# rom.net
KiCad netlist of a schematic drawn in EAGLE
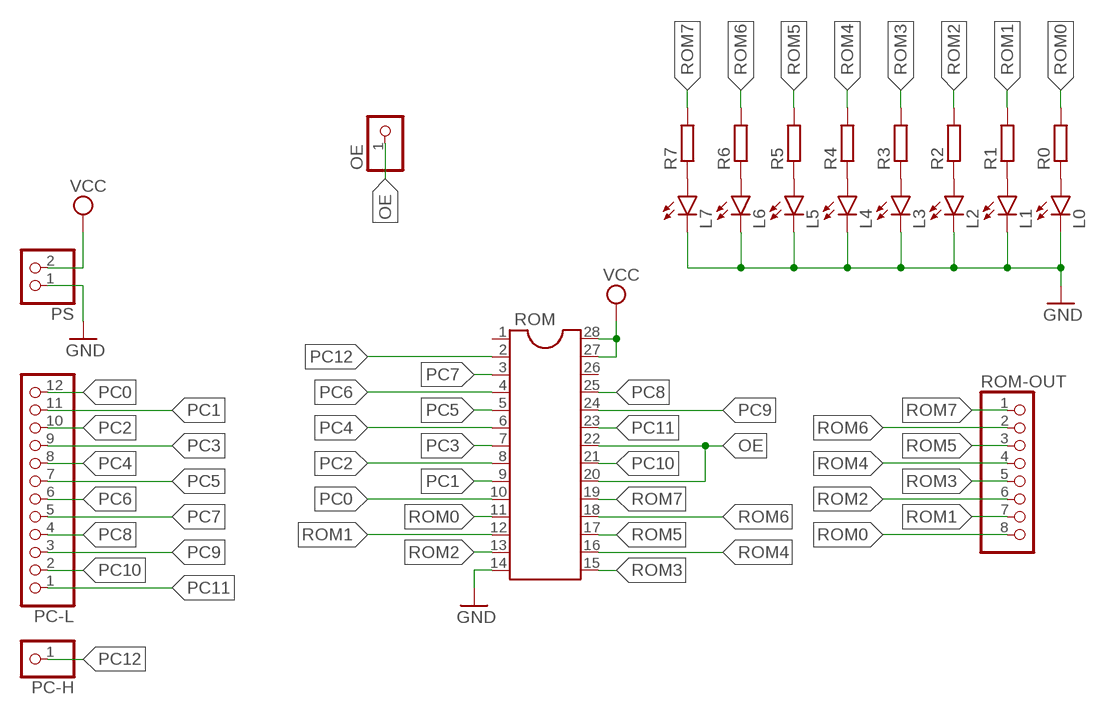
[diagram p0: schematic, sheet 1]

(export (version "E")
  (design (tool "Eeschema 10.0.6"))
  (components
    (comp (ref "L0")
      (value "LED5MM")
      (footprint "eagle-import:LED5MM")
      (libsource (lib "eagle-import") (part "LED5MM"))
    )
    (comp (ref "L1")
      (value "LED5MM")
      (footprint "eagle-import:LED5MM")
      (libsource (lib "eagle-import") (part "LED5MM"))
    )
    (comp (ref "L2")
      (value "LED5MM")
      (footprint "eagle-import:LED5MM")
      (libsource (lib "eagle-import") (part "LED5MM"))
    )
    (comp (ref "L3")
      (value "LED5MM")
      (footprint "eagle-import:LED5MM")
      (libsource (lib "eagle-import") (part "LED5MM"))
    )
    (comp (ref "L4")
      (value "LED5MM")
      (footprint "eagle-import:LED5MM")
      (libsource (lib "eagle-import") (part "LED5MM"))
    )
    (comp (ref "L5")
      (value "LED5MM")
      (footprint "eagle-import:LED5MM")
      (libsource (lib "eagle-import") (part "LED5MM"))
    )
    (comp (ref "L6")
      (value "LED5MM")
      (footprint "eagle-import:LED5MM")
      (libsource (lib "eagle-import") (part "LED5MM"))
    )
    (comp (ref "L7")
      (value "LED5MM")
      (footprint "eagle-import:LED5MM")
      (libsource (lib "eagle-import") (part "LED5MM"))
    )
    (comp (ref "OE")
      (value "PINHD-1X1")
      (footprint "eagle-import:1X01")
      (libsource (lib "eagle-import") (part "PINHD-1X1"))
    )
    (comp (ref "PC-H")
      (value "PINHD-1X1")
      (footprint "eagle-import:1X01")
      (libsource (lib "eagle-import") (part "PINHD-1X1"))
    )
    (comp (ref "PC-L")
      (value "PINHD-1X12")
      (footprint "eagle-import:1X12")
      (libsource (lib "eagle-import") (part "PINHD-1X12"))
    )
    (comp (ref "PS")
      (value "PINHD-1X2")
      (footprint "eagle-import:1X02")
      (libsource (lib "eagle-import") (part "PINHD-1X2"))
    )
    (comp (ref "R0")
      (value "R-EU_0204/7")
      (footprint "eagle-import:0204_7")
      (libsource (lib "eagle-import") (part "R-EU_0204/7"))
    )
    (comp (ref "R1")
      (value "R-EU_0204/7")
      (footprint "eagle-import:0204_7")
      (libsource (lib "eagle-import") (part "R-EU_0204/7"))
    )
    (comp (ref "R2")
      (value "R-EU_0204/7")
      (footprint "eagle-import:0204_7")
      (libsource (lib "eagle-import") (part "R-EU_0204/7"))
    )
    (comp (ref "R3")
      (value "R-EU_0204/7")
      (footprint "eagle-import:0204_7")
      (libsource (lib "eagle-import") (part "R-EU_0204/7"))
    )
    (comp (ref "R4")
      (value "R-EU_0204/7")
      (footprint "eagle-import:0204_7")
      (libsource (lib "eagle-import") (part "R-EU_0204/7"))
    )
    (comp (ref "R5")
      (value "R-EU_0204/7")
      (footprint "eagle-import:0204_7")
      (libsource (lib "eagle-import") (part "R-EU_0204/7"))
    )
    (comp (ref "R6")
      (value "R-EU_0204/7")
      (footprint "eagle-import:0204_7")
      (libsource (lib "eagle-import") (part "R-EU_0204/7"))
    )
    (comp (ref "R7")
      (value "R-EU_0204/7")
      (footprint "eagle-import:0204_7")
      (libsource (lib "eagle-import") (part "R-EU_0204/7"))
    )
    (comp (ref "ROM")
      (value "DIL28")
      (footprint "eagle-import:DIL28-6")
      (libsource (lib "eagle-import") (part "DIL28"))
    )
    (comp (ref "ROM-OUT")
      (value "PINHD-1X8")
      (footprint "eagle-import:1X08")
      (libsource (lib "eagle-import") (part "PINHD-1X8"))
    )
  )
  (nets
    (net (code "1") (name "GND") (class "Default")
      (node (ref "L0") (pin "K") (pinfunction "C_K") (pintype "passive"))
      (node (ref "L1") (pin "K") (pinfunction "C_K") (pintype "passive"))
      (node (ref "L2") (pin "K") (pinfunction "C_K") (pintype "passive"))
      (node (ref "L3") (pin "K") (pinfunction "C_K") (pintype "passive"))
      (node (ref "L4") (pin "K") (pinfunction "C_K") (pintype "passive"))
      (node (ref "L5") (pin "K") (pinfunction "C_K") (pintype "passive"))
      (node (ref "L6") (pin "K") (pinfunction "C_K") (pintype "passive"))
      (node (ref "L7") (pin "K") (pinfunction "C_K") (pintype "passive"))
      (node (ref "PS") (pin "1") (pinfunction "1_1") (pintype "passive"))
      (node (ref "ROM") (pin "14") (pinfunction "14_14") (pintype "passive"))
    )
    (net (code "2") (name "Net-(L0-PadA)") (class "Default")
      (node (ref "L0") (pin "A") (pinfunction "A_A") (pintype "passive"))
      (node (ref "R0") (pin "1") (pinfunction "1_1") (pintype "passive"))
    )
    (net (code "3") (name "Net-(L1-PadA)") (class "Default")
      (node (ref "L1") (pin "A") (pinfunction "A_A") (pintype "passive"))
      (node (ref "R1") (pin "1") (pinfunction "1_1") (pintype "passive"))
    )
    (net (code "4") (name "Net-(L2-PadA)") (class "Default")
      (node (ref "L2") (pin "A") (pinfunction "A_A") (pintype "passive"))
      (node (ref "R2") (pin "1") (pinfunction "1_1") (pintype "passive"))
    )
    (net (code "5") (name "Net-(L3-PadA)") (class "Default")
      (node (ref "L3") (pin "A") (pinfunction "A_A") (pintype "passive"))
      (node (ref "R3") (pin "1") (pinfunction "1_1") (pintype "passive"))
    )
    (net (code "6") (name "Net-(L4-PadA)") (class "Default")
      (node (ref "L4") (pin "A") (pinfunction "A_A") (pintype "passive"))
      (node (ref "R4") (pin "1") (pinfunction "1_1") (pintype "passive"))
    )
    (net (code "7") (name "Net-(L5-PadA)") (class "Default")
      (node (ref "L5") (pin "A") (pinfunction "A_A") (pintype "passive"))
      (node (ref "R5") (pin "1") (pinfunction "1_1") (pintype "passive"))
    )
    (net (code "8") (name "Net-(L6-PadA)") (class "Default")
      (node (ref "L6") (pin "A") (pinfunction "A_A") (pintype "passive"))
      (node (ref "R6") (pin "1") (pinfunction "1_1") (pintype "passive"))
    )
    (net (code "9") (name "Net-(L7-PadA)") (class "Default")
      (node (ref "L7") (pin "A") (pinfunction "A_A") (pintype "passive"))
      (node (ref "R7") (pin "1") (pinfunction "1_1") (pintype "passive"))
    )
    (net (code "10") (name "OE") (class "Default")
      (node (ref "OE") (pin "1") (pinfunction "1_1") (pintype "passive"))
      (node (ref "ROM") (pin "20") (pinfunction "20_20") (pintype "passive"))
      (node (ref "ROM") (pin "22") (pinfunction "22_22") (pintype "passive"))
    )
    (net (code "11") (name "PC0") (class "Default")
      (node (ref "PC-L") (pin "12") (pinfunction "12_12") (pintype "passive"))
      (node (ref "ROM") (pin "10") (pinfunction "10_10") (pintype "passive"))
    )
    (net (code "12") (name "PC1") (class "Default")
      (node (ref "PC-L") (pin "11") (pinfunction "11_11") (pintype "passive"))
      (node (ref "ROM") (pin "9") (pinfunction "9_9") (pintype "passive"))
    )
    (net (code "13") (name "PC2") (class "Default")
      (node (ref "PC-L") (pin "10") (pinfunction "10_10") (pintype "passive"))
      (node (ref "ROM") (pin "8") (pinfunction "8_8") (pintype "passive"))
    )
    (net (code "14") (name "PC3") (class "Default")
      (node (ref "PC-L") (pin "9") (pinfunction "9_9") (pintype "passive"))
      (node (ref "ROM") (pin "7") (pinfunction "7_7") (pintype "passive"))
    )
    (net (code "15") (name "PC4") (class "Default")
      (node (ref "PC-L") (pin "8") (pinfunction "8_8") (pintype "passive"))
      (node (ref "ROM") (pin "6") (pinfunction "6_6") (pintype "passive"))
    )
    (net (code "16") (name "PC5") (class "Default")
      (node (ref "PC-L") (pin "7") (pinfunction "7_7") (pintype "passive"))
      (node (ref "ROM") (pin "5") (pinfunction "5_5") (pintype "passive"))
    )
    (net (code "17") (name "PC6") (class "Default")
      (node (ref "PC-L") (pin "6") (pinfunction "6_6") (pintype "passive"))
      (node (ref "ROM") (pin "4") (pinfunction "4_4") (pintype "passive"))
    )
    (net (code "18") (name "PC7") (class "Default")
      (node (ref "PC-L") (pin "5") (pinfunction "5_5") (pintype "passive"))
      (node (ref "ROM") (pin "3") (pinfunction "3_3") (pintype "passive"))
    )
    (net (code "19") (name "PC8") (class "Default")
      (node (ref "PC-L") (pin "4") (pinfunction "4_4") (pintype "passive"))
      (node (ref "ROM") (pin "25") (pinfunction "25_25") (pintype "passive"))
    )
    (net (code "20") (name "PC9") (class "Default")
      (node (ref "PC-L") (pin "3") (pinfunction "3_3") (pintype "passive"))
      (node (ref "ROM") (pin "24") (pinfunction "24_24") (pintype "passive"))
    )
    (net (code "21") (name "PC10") (class "Default")
      (node (ref "PC-L") (pin "2") (pinfunction "2_2") (pintype "passive"))
      (node (ref "ROM") (pin "21") (pinfunction "21_21") (pintype "passive"))
    )
    (net (code "22") (name "PC11") (class "Default")
      (node (ref "PC-L") (pin "1") (pinfunction "1_1") (pintype "passive"))
      (node (ref "ROM") (pin "23") (pinfunction "23_23") (pintype "passive"))
    )
    (net (code "23") (name "PC12") (class "Default")
      (node (ref "PC-H") (pin "1") (pinfunction "1_1") (pintype "passive"))
      (node (ref "ROM") (pin "2") (pinfunction "2_2") (pintype "passive"))
    )
    (net (code "24") (name "ROM0") (class "Default")
      (node (ref "R0") (pin "2") (pinfunction "2_2") (pintype "passive"))
      (node (ref "ROM") (pin "11") (pinfunction "11_11") (pintype "passive"))
      (node (ref "ROM-OUT") (pin "8") (pinfunction "8_8") (pintype "passive"))
    )
    (net (code "25") (name "ROM1") (class "Default")
      (node (ref "R1") (pin "2") (pinfunction "2_2") (pintype "passive"))
      (node (ref "ROM") (pin "12") (pinfunction "12_12") (pintype "passive"))
      (node (ref "ROM-OUT") (pin "7") (pinfunction "7_7") (pintype "passive"))
    )
    (net (code "26") (name "ROM2") (class "Default")
      (node (ref "R2") (pin "2") (pinfunction "2_2") (pintype "passive"))
      (node (ref "ROM") (pin "13") (pinfunction "13_13") (pintype "passive"))
      (node (ref "ROM-OUT") (pin "6") (pinfunction "6_6") (pintype "passive"))
    )
    (net (code "27") (name "ROM3") (class "Default")
      (node (ref "R3") (pin "2") (pinfunction "2_2") (pintype "passive"))
      (node (ref "ROM") (pin "15") (pinfunction "15_15") (pintype "passive"))
      (node (ref "ROM-OUT") (pin "5") (pinfunction "5_5") (pintype "passive"))
    )
    (net (code "28") (name "ROM4") (class "Default")
      (node (ref "R4") (pin "2") (pinfunction "2_2") (pintype "passive"))
      (node (ref "ROM") (pin "16") (pinfunction "16_16") (pintype "passive"))
      (node (ref "ROM-OUT") (pin "4") (pinfunction "4_4") (pintype "passive"))
    )
    (net (code "29") (name "ROM5") (class "Default")
      (node (ref "R5") (pin "2") (pinfunction "2_2") (pintype "passive"))
      (node (ref "ROM") (pin "17") (pinfunction "17_17") (pintype "passive"))
      (node (ref "ROM-OUT") (pin "3") (pinfunction "3_3") (pintype "passive"))
    )
    (net (code "30") (name "ROM6") (class "Default")
      (node (ref "R6") (pin "2") (pinfunction "2_2") (pintype "passive"))
      (node (ref "ROM") (pin "18") (pinfunction "18_18") (pintype "passive"))
      (node (ref "ROM-OUT") (pin "2") (pinfunction "2_2") (pintype "passive"))
    )
    (net (code "31") (name "ROM7") (class "Default")
      (node (ref "R7") (pin "2") (pinfunction "2_2") (pintype "passive"))
      (node (ref "ROM") (pin "19") (pinfunction "19_19") (pintype "passive"))
      (node (ref "ROM-OUT") (pin "1") (pinfunction "1_1") (pintype "passive"))
    )
    (net (code "32") (name "VCC") (class "Default")
      (node (ref "PS") (pin "2") (pinfunction "2_2") (pintype "passive"))
      (node (ref "ROM") (pin "27") (pinfunction "27_27") (pintype "passive"))
      (node (ref "ROM") (pin "28") (pinfunction "28_28") (pintype "passive"))
    )
    (net (code "33") (name "unconnected-(ROM-Pad1)") (class "Default")
      (node (ref "ROM") (pin "1") (pinfunction "1_1") (pintype "passive"))
    )
    (net (code "34") (name "unconnected-(ROM-Pad26)") (class "Default")
      (node (ref "ROM") (pin "26") (pinfunction "26_26") (pintype "passive"))
    )
  )
)
